# Rocketometer2148.net
KiCad netlist of a schematic drawn in EAGLE
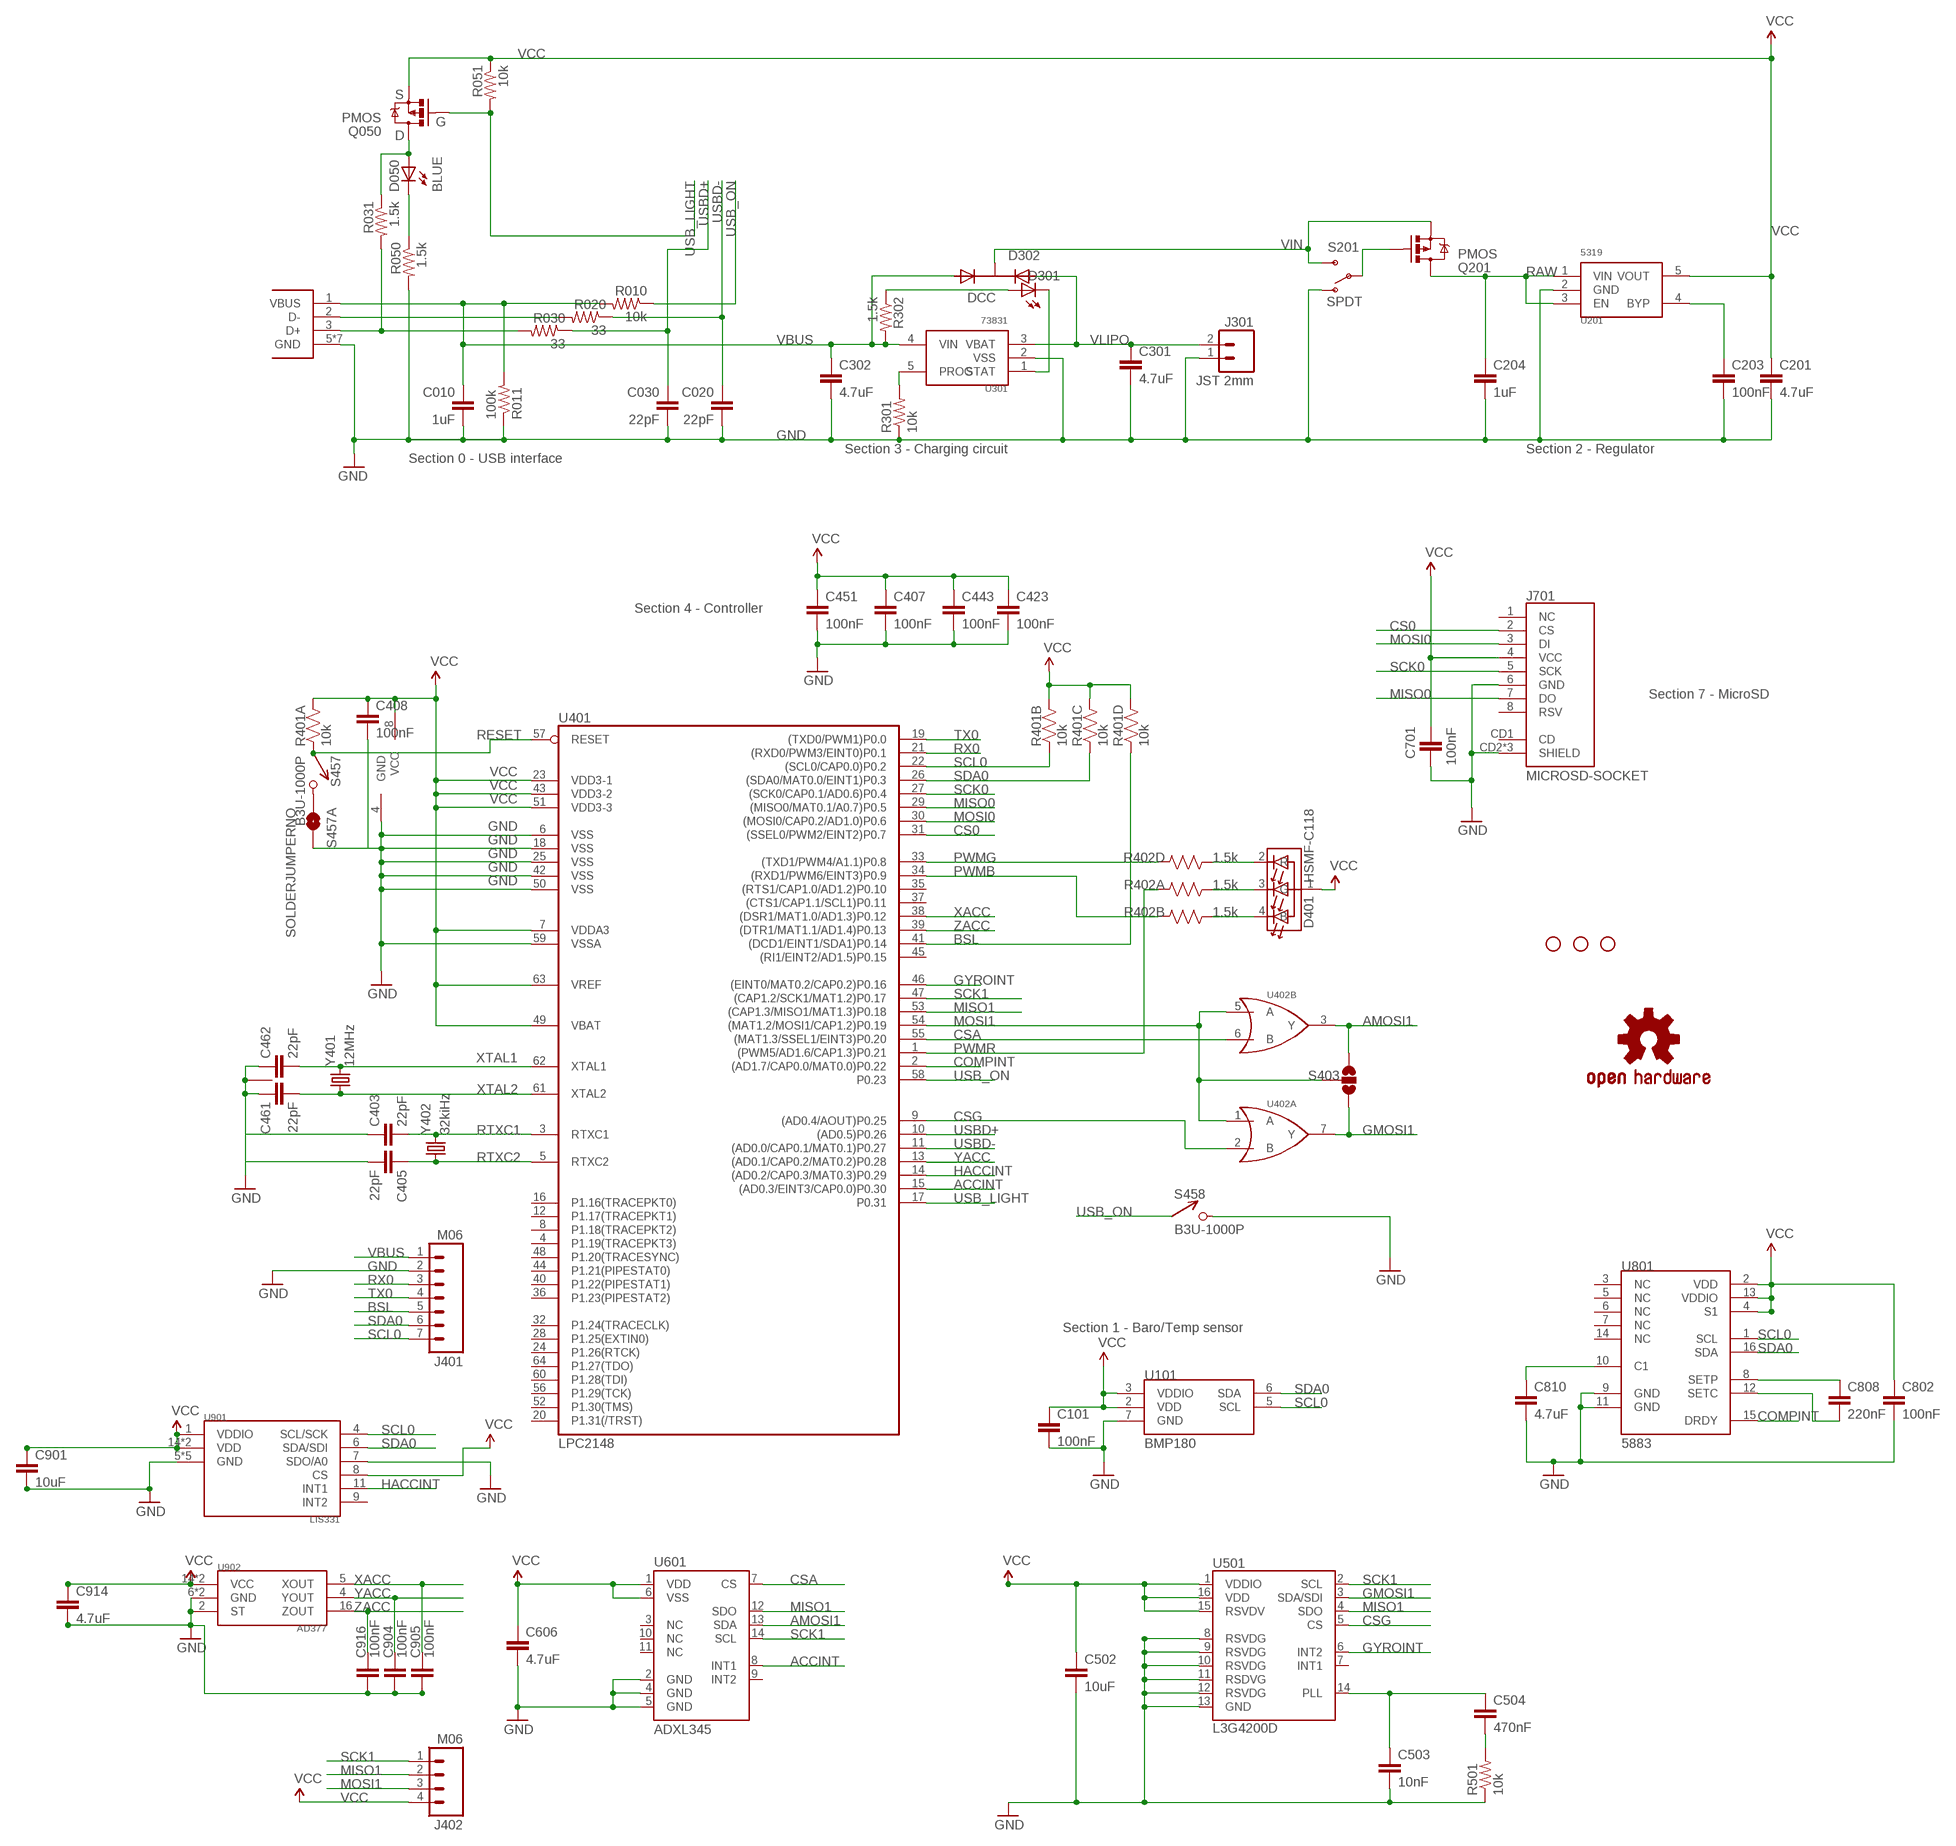
[diagram p0: schematic, sheet 1]

(export (version "E")
  (design (tool "Eeschema 10.0.6"))
  (components
    (comp (ref "C010")
      (value "1uF")
      (footprint "eagle-import:0402-CAP")
      (libsource (lib "eagle-import") (part "CAP0402-CAP"))
    )
    (comp (ref "C020")
      (value "22pF")
      (footprint "eagle-import:0402-CAP")
      (libsource (lib "eagle-import") (part "CAP0402-CAP"))
    )
    (comp (ref "C030")
      (value "22pF")
      (footprint "eagle-import:0402-CAP")
      (libsource (lib "eagle-import") (part "CAP0402-CAP"))
    )
    (comp (ref "C101")
      (value "100nF")
      (footprint "eagle-import:0402-CAP")
      (libsource (lib "eagle-import") (part "CAP0402-CAP"))
    )
    (comp (ref "C201")
      (value "4.7uF")
      (footprint "eagle-import:0402-CAP")
      (libsource (lib "eagle-import") (part "CAP0402-CAP"))
    )
    (comp (ref "C203")
      (value "100nF")
      (footprint "eagle-import:0402-CAP")
      (libsource (lib "eagle-import") (part "CAP0402-CAP"))
    )
    (comp (ref "C204")
      (value "1uF")
      (footprint "eagle-import:0402-CAP")
      (libsource (lib "eagle-import") (part "CAP0402-CAP"))
    )
    (comp (ref "C301")
      (value "4.7uF")
      (footprint "eagle-import:0402-CAP")
      (libsource (lib "eagle-import") (part "CAP0402-CAP"))
    )
    (comp (ref "C302")
      (value "4.7uF")
      (footprint "eagle-import:0402-CAP")
      (libsource (lib "eagle-import") (part "CAP0402-CAP"))
    )
    (comp (ref "C403")
      (value "22pF")
      (footprint "eagle-import:0402-CAP")
      (libsource (lib "eagle-import") (part "CAP0402-CAP"))
    )
    (comp (ref "C405")
      (value "22pF")
      (footprint "eagle-import:0402-CAP")
      (libsource (lib "eagle-import") (part "CAP0402-CAP"))
    )
    (comp (ref "C407")
      (value "100nF")
      (footprint "eagle-import:0402-CAP")
      (libsource (lib "eagle-import") (part "CAP0402-CAP"))
    )
    (comp (ref "C408")
      (value "100nF")
      (footprint "eagle-import:0402-CAP")
      (libsource (lib "eagle-import") (part "CAP0402-CAP"))
    )
    (comp (ref "C423")
      (value "100nF")
      (footprint "eagle-import:0402-CAP")
      (libsource (lib "eagle-import") (part "CAP0402-CAP"))
    )
    (comp (ref "C443")
      (value "100nF")
      (footprint "eagle-import:0402-CAP")
      (libsource (lib "eagle-import") (part "CAP0402-CAP"))
    )
    (comp (ref "C451")
      (value "100nF")
      (footprint "eagle-import:0402-CAP")
      (libsource (lib "eagle-import") (part "CAP0402-CAP"))
    )
    (comp (ref "C461")
      (value "22pF")
      (footprint "eagle-import:0402-CAP")
      (libsource (lib "eagle-import") (part "CAP0402-CAP"))
    )
    (comp (ref "C462")
      (value "22pF")
      (footprint "eagle-import:0402-CAP")
      (libsource (lib "eagle-import") (part "CAP0402-CAP"))
    )
    (comp (ref "C502")
      (value "10uF")
      (footprint "eagle-import:0603-CAP")
      (libsource (lib "eagle-import") (part "CAP0603-CAP"))
    )
    (comp (ref "C503")
      (value "10nF")
      (footprint "eagle-import:0402-CAP")
      (libsource (lib "eagle-import") (part "CAP0402-CAP"))
    )
    (comp (ref "C504")
      (value "470nF")
      (footprint "eagle-import:0402-CAP")
      (libsource (lib "eagle-import") (part "CAP0402-CAP"))
    )
    (comp (ref "C606")
      (value "4.7uF")
      (footprint "eagle-import:0402-CAP")
      (libsource (lib "eagle-import") (part "CAP0402-CAP"))
    )
    (comp (ref "C701")
      (value "100nF")
      (footprint "eagle-import:0402-CAP")
      (libsource (lib "eagle-import") (part "CAP0402-CAP"))
    )
    (comp (ref "C802")
      (value "100nF")
      (footprint "eagle-import:0402-CAP")
      (libsource (lib "eagle-import") (part "CAP0402-CAP"))
    )
    (comp (ref "C808")
      (value "220nF")
      (footprint "eagle-import:0402-CAP")
      (libsource (lib "eagle-import") (part "CAP0402-CAP"))
    )
    (comp (ref "C810")
      (value "4.7uF")
      (footprint "eagle-import:0402-CAP")
      (libsource (lib "eagle-import") (part "CAP0402-CAP"))
    )
    (comp (ref "C901")
      (value "10uF")
      (footprint "eagle-import:0603-CAP")
      (libsource (lib "eagle-import") (part "CAP0603-CAP"))
    )
    (comp (ref "C904")
      (value "100nF")
      (footprint "eagle-import:0402-CAP")
      (libsource (lib "eagle-import") (part "CAP0402-CAP"))
    )
    (comp (ref "C905")
      (value "100nF")
      (footprint "eagle-import:0402-CAP")
      (libsource (lib "eagle-import") (part "CAP0402-CAP"))
    )
    (comp (ref "C914")
      (value "4.7uF")
      (footprint "eagle-import:0402-CAP")
      (libsource (lib "eagle-import") (part "CAP0402-CAP"))
    )
    (comp (ref "C916")
      (value "100nF")
      (footprint "eagle-import:0402-CAP")
      (libsource (lib "eagle-import") (part "CAP0402-CAP"))
    )
    (comp (ref "D050")
      (value "BLUE")
      (footprint "eagle-import:LED-0603")
      (libsource (lib "eagle-import") (part "LED0603"))
    )
    (comp (ref "D301")
      (value "YELLOW")
      (footprint "eagle-import:LED-0603")
      (libsource (lib "eagle-import") (part "LED0603"))
    )
    (comp (ref "D302")
      (value "DCC")
      (footprint "eagle-import:SOT-23-3")
      (libsource (lib "eagle-import") (part "PMEG2005CT"))
    )
    (comp (ref "D401")
      (value "HSMF-C118")
      (footprint "eagle-import:HSMF-C118")
      (libsource (lib "eagle-import") (part "HSMF-C118"))
    )
    (comp (ref "J001")
      (value "USB_MICROB_JST")
      (footprint "eagle-import:UB-MC5BR3-SD204-4S")
      (libsource (lib "eagle-import") (part "USB_MICROB_JST"))
    )
    (comp (ref "J301")
      (value "JST 2mm")
      (footprint "eagle-import:JST-2-SMD")
      (libsource (lib "eagle-import") (part "M02-JST-2MM-SMT"))
    )
    (comp (ref "J401")
      (value "M06")
      (footprint "eagle-import:1X07")
      (libsource (lib "eagle-import") (part "M07"))
    )
    (comp (ref "J402")
      (value "M06")
      (footprint "eagle-import:1X04")
      (libsource (lib "eagle-import") (part "M04PTH"))
    )
    (comp (ref "J701")
      (value "MICROSD-SOCKET")
      (footprint "eagle-import:MICROSD-SOCKET-PP")
      (libsource (lib "eagle-import") (part "MICROSD-SOCKET"))
    )
    (comp (ref "JP1")
      (value "STAND-OFFTIGHT")
      (footprint "eagle-import:STAND-OFF-TIGHT")
      (libsource (lib "eagle-import") (part "STAND-OFFTIGHT"))
    )
    (comp (ref "JP2")
      (value "STAND-OFFTIGHT")
      (footprint "eagle-import:STAND-OFF-TIGHT")
      (libsource (lib "eagle-import") (part "STAND-OFFTIGHT"))
    )
    (comp (ref "JP3")
      (value "STAND-OFFTIGHT")
      (footprint "eagle-import:STAND-OFF-TIGHT")
      (libsource (lib "eagle-import") (part "STAND-OFFTIGHT"))
    )
    (comp (ref "Q050")
      (value "PMOS")
      (footprint "eagle-import:SOT23-3")
      (libsource (lib "eagle-import") (part "MOSFET-PCHANNELSMD"))
    )
    (comp (ref "Q201")
      (value "PMOS")
      (footprint "eagle-import:SOT23-3")
      (libsource (lib "eagle-import") (part "MOSFET-PCHANNELSMD"))
    )
    (comp (ref "R010")
      (value "10k")
      (footprint "eagle-import:0402-RES")
      (libsource (lib "eagle-import") (part "RESISTOR0402-RES"))
    )
    (comp (ref "R011")
      (value "100k")
      (footprint "eagle-import:0402-RES")
      (libsource (lib "eagle-import") (part "RESISTOR0402-RES"))
    )
    (comp (ref "R020")
      (value "33")
      (footprint "eagle-import:0402-RES")
      (libsource (lib "eagle-import") (part "RESISTOR0402-RES"))
    )
    (comp (ref "R030")
      (value "33")
      (footprint "eagle-import:0402-RES")
      (libsource (lib "eagle-import") (part "RESISTOR0402-RES"))
    )
    (comp (ref "R031")
      (value "1.5k")
      (footprint "eagle-import:0402-RES")
      (libsource (lib "eagle-import") (part "RESISTOR0402-RES"))
    )
    (comp (ref "R050")
      (value "1.5k")
      (footprint "eagle-import:0402-RES")
      (libsource (lib "eagle-import") (part "RESISTOR0402-RES"))
    )
    (comp (ref "R051")
      (value "10k")
      (footprint "eagle-import:0402-RES")
      (libsource (lib "eagle-import") (part "RESISTOR0402-RES"))
    )
    (comp (ref "R301")
      (value "10k")
      (footprint "eagle-import:0402-RES")
      (libsource (lib "eagle-import") (part "RESISTOR0402-RES"))
    )
    (comp (ref "R302")
      (value "1.5k")
      (footprint "eagle-import:0402-RES")
      (libsource (lib "eagle-import") (part "RESISTOR0402-RES"))
    )
    (comp (ref "R401")
      (value "10k")
      (footprint "eagle-import:CRA04")
      (fields (field (name "DIGIKEY") "CRA4S810KCT-ND"))
      (libsource (lib "eagle-import") (part "RP404"))
    )
    (comp (ref "R402")
      (value "1.5k")
      (footprint "eagle-import:CRA04")
      (fields (field (name "DIGIKEY") "CRA4S81.5KCT-ND"))
      (libsource (lib "eagle-import") (part "RP404"))
    )
    (comp (ref "R501")
      (value "10k")
      (footprint "eagle-import:0402-RES")
      (libsource (lib "eagle-import") (part "RESISTOR0402-RES"))
    )
    (comp (ref "S201")
      (value "SPDT")
      (footprint "eagle-import:AYZ0202")
      (libsource (lib "eagle-import") (part "SWITCH-SPSTSMD"))
    )
    (comp (ref "S403")
      (value "SOLDERJUMPER_2WAYS")
      (footprint "eagle-import:SJ_3")
      (libsource (lib "eagle-import") (part "SOLDERJUMPER_2WAYS"))
    )
    (comp (ref "S457")
      (value "B3U-1000P")
      (footprint "eagle-import:B3U-1000P")
      (libsource (lib "eagle-import") (part "B3U-1000P"))
    )
    (comp (ref "S457A")
      (value "SOLDERJUMPERNO")
      (footprint "eagle-import:SJ_2S-NO")
      (libsource (lib "eagle-import") (part "SOLDERJUMPERNO"))
    )
    (comp (ref "S458")
      (value "B3U-1000P")
      (footprint "eagle-import:B3U-1000P")
      (libsource (lib "eagle-import") (part "B3U-1000P"))
    )
    (comp (ref "U$2")
      (value "OSHW-LOGOS")
      (footprint "eagle-import:OSHW-LOGO-S")
      (libsource (lib "eagle-import") (part "OSHW-LOGOS"))
    )
    (comp (ref "U101")
      (value "BMP180")
      (footprint "eagle-import:BMP180")
      (libsource (lib "eagle-import") (part "BMP180"))
    )
    (comp (ref "U201")
      (value "5319")
      (footprint "eagle-import:SOT-23-5")
      (libsource (lib "eagle-import") (part "MIC5319D5"))
    )
    (comp (ref "U301")
      (value "73831")
      (footprint "eagle-import:SOT-23-5")
      (libsource (lib "eagle-import") (part "MCP73831"))
    )
    (comp (ref "U401")
      (value "LPC2148")
      (footprint "eagle-import:SQFP-S-10X10-64")
      (libsource (lib "eagle-import") (part "LPC213X"))
    )
    (comp (ref "U402")
      (value "7432")
      (footprint "eagle-import:DCU_8")
      (fields (field (name "DIGIKEY") "296-13268-1-ND"))
      (libsource (lib "eagle-import") (part "SN74LVC2G32"))
    )
    (comp (ref "U501")
      (value "L3G4200D")
      (footprint "eagle-import:LGA16-4X4")
      (libsource (lib "eagle-import") (part "L3G4200D"))
    )
    (comp (ref "U601")
      (value "ADXL345")
      (footprint "eagle-import:LGA14")
      (libsource (lib "eagle-import") (part "ADXL345"))
    )
    (comp (ref "U801")
      (value "5883")
      (footprint "eagle-import:16LPCC")
      (libsource (lib "eagle-import") (part "HMC5883LSMD"))
    )
    (comp (ref "U901")
      (value "LIS331")
      (footprint "eagle-import:LLGA16")
      (libsource (lib "eagle-import") (part "H3LIS331DL"))
    )
    (comp (ref "U902")
      (value "AD377")
      (footprint "eagle-import:ADXL377")
      (libsource (lib "eagle-import") (part "ADXL377"))
    )
    (comp (ref "Y401")
      (value "12MHz")
      (footprint "eagle-import:CRYSTAL_SMD_2MM_2_5MM")
      (libsource (lib "eagle-import") (part "CX2520"))
    )
    (comp (ref "Y402")
      (value "32kiHz")
      (footprint "eagle-import:ABS06")
      (libsource (lib "eagle-import") (part "ABS06"))
    )
  )
  (nets
    (net (code "1") (name "/ACCINT") (class "Default")
      (node (ref "U401") (pin "15") (pinfunction "(AD0.3/EINT3/CAP0.0)P0.30_15") (pintype "bidirectional"))
      (node (ref "U601") (pin "8") (pinfunction "INT1_8") (pintype "bidirectional"))
    )
    (net (code "2") (name "/AMOSI1") (class "Default")
      (node (ref "S403") (pin "1") (pinfunction "1_1") (pintype "passive"))
      (node (ref "U402") (pin "3") (pinfunction "Y_3") (pintype "bidirectional"))
      (node (ref "U601") (pin "13") (pinfunction "SDA_13") (pintype "bidirectional"))
    )
    (net (code "3") (name "/BSL") (class "Default")
      (node (ref "J401") (pin "5") (pinfunction "5_5") (pintype "passive"))
      (node (ref "R401") (pin "4") (pinfunction "1_4") (pintype "passive"))
      (node (ref "U401") (pin "41") (pinfunction "(DCD1/EINT1/SDA1)P0.14_41") (pintype "bidirectional"))
    )
    (net (code "4") (name "/COMPINT") (class "Default")
      (node (ref "U401") (pin "2") (pinfunction "(AD1.7/CAP0.0/MAT0.0)P0.22_2") (pintype "bidirectional"))
      (node (ref "U801") (pin "15") (pinfunction "DRDY_15") (pintype "bidirectional"))
    )
    (net (code "5") (name "/CS0") (class "Default")
      (node (ref "J701") (pin "2") (pinfunction "CS_2") (pintype "bidirectional"))
      (node (ref "U401") (pin "31") (pinfunction "(SSEL0/PWM2/EINT2)P0.7_31") (pintype "bidirectional"))
    )
    (net (code "6") (name "/CSA") (class "Default")
      (node (ref "U401") (pin "55") (pinfunction "(MAT1.3/SSEL1/EINT3)P0.20_55") (pintype "bidirectional"))
      (node (ref "U402") (pin "6") (pinfunction "B_6") (pintype "bidirectional"))
      (node (ref "U601") (pin "7") (pinfunction "CS_7") (pintype "bidirectional"))
    )
    (net (code "7") (name "/CSG") (class "Default")
      (node (ref "U401") (pin "9") (pinfunction "(AD0.4/AOUT)P0.25_9") (pintype "bidirectional"))
      (node (ref "U402") (pin "2") (pinfunction "B_2") (pintype "bidirectional"))
      (node (ref "U501") (pin "5") (pinfunction "CS_5") (pintype "bidirectional"))
    )
    (net (code "8") (name "/GMOSI1") (class "Default")
      (node (ref "S403") (pin "3") (pinfunction "3_3") (pintype "passive"))
      (node (ref "U402") (pin "7") (pinfunction "Y_7") (pintype "bidirectional"))
      (node (ref "U501") (pin "3") (pinfunction "SDA/SDI_3") (pintype "bidirectional"))
    )
    (net (code "9") (name "/GYROINT") (class "Default")
      (node (ref "U401") (pin "46") (pinfunction "(EINT0/MAT0.2/CAP0.2)P0.16_46") (pintype "bidirectional"))
      (node (ref "U501") (pin "6") (pinfunction "INT2_6") (pintype "bidirectional"))
    )
    (net (code "10") (name "/HACCINT") (class "Default")
      (node (ref "U401") (pin "14") (pinfunction "(AD0.2/CAP0.3/MAT0.3)P0.29_14") (pintype "bidirectional"))
      (node (ref "U901") (pin "11") (pinfunction "INT1_11") (pintype "bidirectional"))
    )
    (net (code "11") (name "/MISO0") (class "Default")
      (node (ref "J701") (pin "7") (pinfunction "DO_7") (pintype "bidirectional"))
      (node (ref "U401") (pin "29") (pinfunction "(MISO0/MAT0.1/A0.7)P0.5_29") (pintype "bidirectional"))
    )
    (net (code "12") (name "/MISO1") (class "Default")
      (node (ref "J402") (pin "2") (pinfunction "2_2") (pintype "passive"))
      (node (ref "U401") (pin "53") (pinfunction "(CAP1.3/MISO1/MAT1.3)P0.18_53") (pintype "bidirectional"))
      (node (ref "U501") (pin "4") (pinfunction "SDO_4") (pintype "bidirectional"))
      (node (ref "U601") (pin "12") (pinfunction "SDO_12") (pintype "bidirectional"))
    )
    (net (code "13") (name "/MOSI0") (class "Default")
      (node (ref "J701") (pin "3") (pinfunction "DI_3") (pintype "bidirectional"))
      (node (ref "U401") (pin "30") (pinfunction "(MOSI0/CAP0.2/AD1.0)P0.6_30") (pintype "bidirectional"))
    )
    (net (code "14") (name "/MOSI1") (class "Default")
      (node (ref "J402") (pin "3") (pinfunction "3_3") (pintype "passive"))
      (node (ref "S403") (pin "2") (pinfunction "2_2") (pintype "passive"))
      (node (ref "U401") (pin "54") (pinfunction "(MAT1.2/MOSI1/CAP1.2)P0.19_54") (pintype "bidirectional"))
      (node (ref "U402") (pin "1") (pinfunction "A_1") (pintype "bidirectional"))
      (node (ref "U402") (pin "5") (pinfunction "A_5") (pintype "bidirectional"))
    )
    (net (code "15") (name "/PWMB") (class "Default")
      (node (ref "R402") (pin "7") (pinfunction "2_7") (pintype "passive"))
      (node (ref "U401") (pin "34") (pinfunction "(RXD1/PWM6/EINT3)P0.9_34") (pintype "bidirectional"))
    )
    (net (code "16") (name "/PWMG") (class "Default")
      (node (ref "R402") (pin "5") (pinfunction "2_5") (pintype "passive"))
      (node (ref "U401") (pin "33") (pinfunction "(TXD1/PWM4/A1.1)P0.8_33") (pintype "bidirectional"))
    )
    (net (code "17") (name "/PWMR") (class "Default")
      (node (ref "R402") (pin "8") (pinfunction "2_8") (pintype "passive"))
      (node (ref "U401") (pin "1") (pinfunction "(PWM5/AD1.6/CAP1.3)P0.21_1") (pintype "bidirectional"))
    )
    (net (code "18") (name "/RAW") (class "Default")
      (node (ref "C204") (pin "1") (pinfunction "1_1") (pintype "passive"))
      (node (ref "Q201") (pin "3") (pinfunction "D_3") (pintype "passive"))
      (node (ref "U201") (pin "1") (pinfunction "VIN_1") (pintype "bidirectional"))
      (node (ref "U201") (pin "3") (pinfunction "EN_3") (pintype "bidirectional"))
    )
    (net (code "19") (name "/RESET") (class "Default")
      (node (ref "R401") (pin "1") (pinfunction "1_1") (pintype "passive"))
      (node (ref "S457") (pin "P$1") (pinfunction "1_P$1") (pintype "bidirectional"))
      (node (ref "U401") (pin "57") (pinfunction "RESET_57") (pintype "input"))
    )
    (net (code "20") (name "/RTXC1") (class "Default")
      (node (ref "C403") (pin "2") (pinfunction "2_2") (pintype "passive"))
      (node (ref "U401") (pin "3") (pinfunction "RTXC1_3") (pintype "input"))
      (node (ref "Y402") (pin "2") (pinfunction "2_2") (pintype "passive"))
    )
    (net (code "21") (name "/RTXC2") (class "Default")
      (node (ref "C405") (pin "1") (pinfunction "1_1") (pintype "passive"))
      (node (ref "U401") (pin "5") (pinfunction "RTXC2_5") (pintype "output"))
      (node (ref "Y402") (pin "1") (pinfunction "1_1") (pintype "passive"))
    )
    (net (code "22") (name "/RX0") (class "Default")
      (node (ref "J401") (pin "3") (pinfunction "3_3") (pintype "passive"))
      (node (ref "U401") (pin "21") (pinfunction "(RXD0/PWM3/EINT0)P0.1_21") (pintype "bidirectional"))
    )
    (net (code "23") (name "/SCK0") (class "Default")
      (node (ref "J701") (pin "5") (pinfunction "SCK_5") (pintype "bidirectional"))
      (node (ref "U401") (pin "27") (pinfunction "(SCK0/CAP0.1/AD0.6)P0.4_27") (pintype "bidirectional"))
    )
    (net (code "24") (name "/SCK1") (class "Default")
      (node (ref "J402") (pin "1") (pinfunction "1_1") (pintype "passive"))
      (node (ref "U401") (pin "47") (pinfunction "(CAP1.2/SCK1/MAT1.2)P0.17_47") (pintype "bidirectional"))
      (node (ref "U501") (pin "2") (pinfunction "SCL_2") (pintype "bidirectional"))
      (node (ref "U601") (pin "14") (pinfunction "SCL_14") (pintype "bidirectional"))
    )
    (net (code "25") (name "/SCL0") (class "Default")
      (node (ref "J401") (pin "7") (pinfunction "7_7") (pintype "passive"))
      (node (ref "R401") (pin "2") (pinfunction "1_2") (pintype "passive"))
      (node (ref "U101") (pin "5") (pinfunction "SCL_5") (pintype "input"))
      (node (ref "U401") (pin "22") (pinfunction "(SCL0/CAP0.0)P0.2_22") (pintype "bidirectional"))
      (node (ref "U801") (pin "1") (pinfunction "SCL_1") (pintype "bidirectional"))
      (node (ref "U901") (pin "4") (pinfunction "SCL/SCK_4") (pintype "bidirectional"))
    )
    (net (code "26") (name "/SDA0") (class "Default")
      (node (ref "J401") (pin "6") (pinfunction "6_6") (pintype "passive"))
      (node (ref "R401") (pin "3") (pinfunction "1_3") (pintype "passive"))
      (node (ref "U101") (pin "6") (pinfunction "SDA_6") (pintype "bidirectional"))
      (node (ref "U401") (pin "26") (pinfunction "(SDA0/MAT0.0/EINT1)P0.3_26") (pintype "bidirectional"))
      (node (ref "U801") (pin "16") (pinfunction "SDA_16") (pintype "bidirectional"))
      (node (ref "U901") (pin "6") (pinfunction "SDA/SDI_6") (pintype "bidirectional"))
    )
    (net (code "27") (name "/TX0") (class "Default")
      (node (ref "J401") (pin "4") (pinfunction "4_4") (pintype "passive"))
      (node (ref "U401") (pin "19") (pinfunction "(TXD0/PWM1)P0.0_19") (pintype "bidirectional"))
    )
    (net (code "28") (name "/USBD+") (class "Default")
      (node (ref "C030") (pin "1") (pinfunction "1_1") (pintype "passive"))
      (node (ref "R030") (pin "1") (pinfunction "1_1") (pintype "passive"))
      (node (ref "U401") (pin "10") (pinfunction "(AD0.5)P0.26_10") (pintype "bidirectional"))
    )
    (net (code "29") (name "/USBD-") (class "Default")
      (node (ref "C020") (pin "1") (pinfunction "1_1") (pintype "passive"))
      (node (ref "R020") (pin "1") (pinfunction "1_1") (pintype "passive"))
      (node (ref "U401") (pin "11") (pinfunction "(AD0.0/CAP0.1/MAT0.1)P0.27_11") (pintype "bidirectional"))
    )
    (net (code "30") (name "/USB_LIGHT") (class "Default")
      (node (ref "Q050") (pin "1") (pinfunction "G_1") (pintype "passive"))
      (node (ref "R051") (pin "2") (pinfunction "2_2") (pintype "passive"))
      (node (ref "U401") (pin "17") (pinfunction "P0.31_17") (pintype "output"))
    )
    (net (code "31") (name "/USB_ON") (class "Default")
      (node (ref "R010") (pin "1") (pinfunction "1_1") (pintype "passive"))
      (node (ref "S458") (pin "P$1") (pinfunction "1_P$1") (pintype "bidirectional"))
      (node (ref "U401") (pin "58") (pinfunction "P0.23_58") (pintype "bidirectional"))
    )
    (net (code "32") (name "/VBUS") (class "Default")
      (node (ref "C010") (pin "1") (pinfunction "1_1") (pintype "passive"))
      (node (ref "C302") (pin "1") (pinfunction "1_1") (pintype "passive"))
      (node (ref "D302") (pin "1") (pinfunction "A1_1") (pintype "passive"))
      (node (ref "J001") (pin "1") (pinfunction "VBUS_1") (pintype "bidirectional"))
      (node (ref "J401") (pin "1") (pinfunction "1_1") (pintype "passive"))
      (node (ref "R010") (pin "2") (pinfunction "2_2") (pintype "passive"))
      (node (ref "R011") (pin "2") (pinfunction "2_2") (pintype "passive"))
      (node (ref "R302") (pin "2") (pinfunction "2_2") (pintype "passive"))
      (node (ref "U301") (pin "4") (pinfunction "VIN_4") (pintype "bidirectional"))
    )
    (net (code "33") (name "/VIN") (class "Default")
      (node (ref "D302") (pin "3") (pinfunction "K_3") (pintype "passive"))
      (node (ref "Q201") (pin "2") (pinfunction "S_2") (pintype "passive"))
      (node (ref "S201") (pin "3") (pinfunction "S_3") (pintype "passive"))
    )
    (net (code "34") (name "/VLIPO") (class "Default")
      (node (ref "C301") (pin "1") (pinfunction "1_1") (pintype "passive"))
      (node (ref "D302") (pin "2") (pinfunction "A2_2") (pintype "passive"))
      (node (ref "J301") (pin "2") (pinfunction "2_2") (pintype "passive"))
      (node (ref "U301") (pin "3") (pinfunction "VBAT_3") (pintype "bidirectional"))
    )
    (net (code "35") (name "/XACC") (class "Default")
      (node (ref "C905") (pin "1") (pinfunction "1_1") (pintype "passive"))
      (node (ref "U401") (pin "38") (pinfunction "(DSR1/MAT1.0/AD1.3)P0.12_38") (pintype "bidirectional"))
      (node (ref "U902") (pin "5") (pinfunction "XOUT_5") (pintype "bidirectional"))
    )
    (net (code "36") (name "/XTAL1") (class "Default")
      (node (ref "C462") (pin "2") (pinfunction "2_2") (pintype "passive"))
      (node (ref "U401") (pin "62") (pinfunction "XTAL1_62") (pintype "input"))
      (node (ref "Y401") (pin "3") (pinfunction "2_3") (pintype "passive"))
    )
    (net (code "37") (name "/XTAL2") (class "Default")
      (node (ref "C461") (pin "2") (pinfunction "2_2") (pintype "passive"))
      (node (ref "U401") (pin "61") (pinfunction "XTAL2_61") (pintype "output"))
      (node (ref "Y401") (pin "1") (pinfunction "1_1") (pintype "passive"))
    )
    (net (code "38") (name "/YACC") (class "Default")
      (node (ref "C904") (pin "1") (pinfunction "1_1") (pintype "passive"))
      (node (ref "U401") (pin "13") (pinfunction "(AD0.1/CAP0.2/MAT0.2)P0.28_13") (pintype "bidirectional"))
      (node (ref "U902") (pin "4") (pinfunction "YOUT_4") (pintype "bidirectional"))
    )
    (net (code "39") (name "/ZACC") (class "Default")
      (node (ref "C916") (pin "1") (pinfunction "1_1") (pintype "passive"))
      (node (ref "U401") (pin "39") (pinfunction "(DTR1/MAT1.1/AD1.4)P0.13_39") (pintype "bidirectional"))
      (node (ref "U902") (pin "16") (pinfunction "ZOUT_16") (pintype "bidirectional"))
    )
    (net (code "40") (name "GND") (class "Default")
      (node (ref "C010") (pin "2") (pinfunction "2_2") (pintype "passive"))
      (node (ref "C020") (pin "2") (pinfunction "2_2") (pintype "passive"))
      (node (ref "C030") (pin "2") (pinfunction "2_2") (pintype "passive"))
      (node (ref "C101") (pin "2") (pinfunction "2_2") (pintype "passive"))
      (node (ref "C201") (pin "2") (pinfunction "2_2") (pintype "passive"))
      (node (ref "C203") (pin "2") (pinfunction "2_2") (pintype "passive"))
      (node (ref "C204") (pin "2") (pinfunction "2_2") (pintype "passive"))
      (node (ref "C301") (pin "2") (pinfunction "2_2") (pintype "passive"))
      (node (ref "C302") (pin "2") (pinfunction "2_2") (pintype "passive"))
      (node (ref "C403") (pin "1") (pinfunction "1_1") (pintype "passive"))
      (node (ref "C405") (pin "2") (pinfunction "2_2") (pintype "passive"))
      (node (ref "C407") (pin "2") (pinfunction "2_2") (pintype "passive"))
      (node (ref "C408") (pin "2") (pinfunction "2_2") (pintype "passive"))
      (node (ref "C423") (pin "2") (pinfunction "2_2") (pintype "passive"))
      (node (ref "C443") (pin "2") (pinfunction "2_2") (pintype "passive"))
      (node (ref "C451") (pin "2") (pinfunction "2_2") (pintype "passive"))
      (node (ref "C461") (pin "1") (pinfunction "1_1") (pintype "passive"))
      (node (ref "C462") (pin "1") (pinfunction "1_1") (pintype "passive"))
      (node (ref "C502") (pin "2") (pinfunction "2_2") (pintype "passive"))
      (node (ref "C503") (pin "2") (pinfunction "2_2") (pintype "passive"))
      (node (ref "C606") (pin "2") (pinfunction "2_2") (pintype "passive"))
      (node (ref "C701") (pin "2") (pinfunction "2_2") (pintype "passive"))
      (node (ref "C802") (pin "2") (pinfunction "2_2") (pintype "passive"))
      (node (ref "C810") (pin "2") (pinfunction "2_2") (pintype "passive"))
      (node (ref "C901") (pin "2") (pinfunction "2_2") (pintype "passive"))
      (node (ref "C904") (pin "2") (pinfunction "2_2") (pintype "passive"))
      (node (ref "C905") (pin "2") (pinfunction "2_2") (pintype "passive"))
      (node (ref "C914") (pin "2") (pinfunction "2_2") (pintype "passive"))
      (node (ref "C916") (pin "2") (pinfunction "2_2") (pintype "passive"))
      (node (ref "J001") (pin "5") (pinfunction "GND_5") (pintype "bidirectional"))
      (node (ref "J001") (pin "P$10") (pinfunction "GND_P$10") (pintype "bidirectional"))
      (node (ref "J001") (pin "P$11") (pinfunction "GND_P$11") (pintype "bidirectional"))
      (node (ref "J001") (pin "P$6") (pinfunction "GND_P$6") (pintype "bidirectional"))
      (node (ref "J001") (pin "P$7") (pinfunction "GND_P$7") (pintype "bidirectional"))
      (node (ref "J001") (pin "P$8") (pinfunction "GND_P$8") (pintype "bidirectional"))
      (node (ref "J001") (pin "P$9") (pinfunction "GND_P$9") (pintype "bidirectional"))
      (node (ref "J301") (pin "1") (pinfunction "1_1") (pintype "passive"))
      (node (ref "J401") (pin "2") (pinfunction "2_2") (pintype "passive"))
      (node (ref "J701") (pin "6") (pinfunction "GND_6") (pintype "bidirectional"))
      (node (ref "J701") (pin "CD2") (pinfunction "SHIELD_CD2") (pintype "bidirectional"))
      (node (ref "J701") (pin "GND1") (pinfunction "SHIELD_GND1") (pintype "bidirectional"))
      (node (ref "J701") (pin "GND3") (pinfunction "SHIELD_GND3") (pintype "bidirectional"))
      (node (ref "R011") (pin "1") (pinfunction "1_1") (pintype "passive"))
      (node (ref "R050") (pin "2") (pinfunction "2_2") (pintype "passive"))
      (node (ref "R301") (pin "1") (pinfunction "1_1") (pintype "passive"))
      (node (ref "R501") (pin "1") (pinfunction "1_1") (pintype "passive"))
      (node (ref "S201") (pin "1") (pinfunction "O_1") (pintype "passive"))
      (node (ref "S457A") (pin "2") (pinfunction "2_2") (pintype "passive"))
      (node (ref "S458") (pin "P$2") (pinfunction "2_P$2") (pintype "bidirectional"))
      (node (ref "U101") (pin "7") (pinfunction "GND_7") (pintype "power_in"))
      (node (ref "U201") (pin "2") (pinfunction "GND_2") (pintype "bidirectional"))
      (node (ref "U301") (pin "2") (pinfunction "VSS_2") (pintype "bidirectional"))
      (node (ref "U401") (pin "18") (pinfunction "VSS_18") (pintype "power_in"))
      (node (ref "U401") (pin "25") (pinfunction "VSS_25") (pintype "power_in"))
      (node (ref "U401") (pin "42") (pinfunction "VSS_42") (pintype "power_in"))
      (node (ref "U401") (pin "50") (pinfunction "VSS_50") (pintype "power_in"))
      (node (ref "U401") (pin "59") (pinfunction "VSSA_59") (pintype "power_in"))
      (node (ref "U401") (pin "6") (pinfunction "VSS_6") (pintype "power_in"))
      (node (ref "U402") (pin "4") (pinfunction "GND_4") (pintype "bidirectional"))
      (node (ref "U501") (pin "10") (pinfunction "RSVDG_10") (pintype "bidirectional"))
      (node (ref "U501") (pin "11") (pinfunction "RSDVG_11") (pintype "bidirectional"))
      (node (ref "U501") (pin "12") (pinfunction "RSVDG_12") (pintype "bidirectional"))
      (node (ref "U501") (pin "13") (pinfunction "GND_13") (pintype "bidirectional"))
      (node (ref "U501") (pin "8") (pinfunction "RSVDG_8") (pintype "bidirectional"))
      (node (ref "U501") (pin "9") (pinfunction "RSVDG_9") (pintype "bidirectional"))
      (node (ref "U601") (pin "2") (pinfunction "GND_2") (pintype "bidirectional"))
      (node (ref "U601") (pin "4") (pinfunction "GND_4") (pintype "bidirectional"))
      (node (ref "U601") (pin "5") (pinfunction "GND_5") (pintype "bidirectional"))
      (node (ref "U801") (pin "11") (pinfunction "GND_11") (pintype "bidirectional"))
      (node (ref "U801") (pin "9") (pinfunction "GND_9") (pintype "bidirectional"))
      (node (ref "U901") (pin "10") (pinfunction "GND_10") (pintype "bidirectional"))
      (node (ref "U901") (pin "12") (pinfunction "GND_12") (pintype "bidirectional"))
      (node (ref "U901") (pin "13") (pinfunction "GND_13") (pintype "bidirectional"))
      (node (ref "U901") (pin "16") (pinfunction "GND_16") (pintype "bidirectional"))
      (node (ref "U901") (pin "5") (pinfunction "GND_5") (pintype "bidirectional"))
      (node (ref "U901") (pin "7") (pinfunction "SDO/A0_7") (pintype "bidirectional"))
      (node (ref "U902") (pin "2") (pinfunction "ST_2") (pintype "bidirectional"))
      (node (ref "U902") (pin "6") (pinfunction "GND_6") (pintype "bidirectional"))
      (node (ref "U902") (pin "7") (pinfunction "GND_7") (pintype "bidirectional"))
      (node (ref "Y401") (pin "2") (pinfunction "1_2") (pintype "bidirectional"))
      (node (ref "Y401") (pin "4") (pinfunction "1_4") (pintype "bidirectional"))
    )
    (net (code "41") (name "Net-(C504-Pad2)") (class "Default")
      (node (ref "C504") (pin "2") (pinfunction "2_2") (pintype "passive"))
      (node (ref "R501") (pin "2") (pinfunction "2_2") (pintype "passive"))
    )
    (net (code "42") (name "Net-(D050-PadC)") (class "Default")
      (node (ref "D050") (pin "C") (pinfunction "C_C") (pintype "passive"))
      (node (ref "R050") (pin "1") (pinfunction "1_1") (pintype "passive"))
    )
    (net (code "43") (name "Net-(D301-PadA)") (class "Default")
      (node (ref "D301") (pin "A") (pinfunction "A_A") (pintype "passive"))
      (node (ref "R302") (pin "1") (pinfunction "1_1") (pintype "passive"))
    )
    (net (code "44") (name "Net-(D401-B)") (class "Default")
      (node (ref "D401") (pin "4") (pinfunction "B_4") (pintype "passive"))
      (node (ref "R402") (pin "2") (pinfunction "1_2") (pintype "passive"))
    )
    (net (code "45") (name "Net-(D401-G)") (class "Default")
      (node (ref "D401") (pin "3") (pinfunction "G_3") (pintype "passive"))
      (node (ref "R402") (pin "1") (pinfunction "1_1") (pintype "passive"))
    )
    (net (code "46") (name "Net-(D401-R)") (class "Default")
      (node (ref "D401") (pin "2") (pinfunction "R_2") (pintype "passive"))
      (node (ref "R402") (pin "4") (pinfunction "1_4") (pintype "passive"))
    )
    (net (code "47") (name "Net-(J001-D+)") (class "Default")
      (node (ref "J001") (pin "3") (pinfunction "D+_3") (pintype "bidirectional"))
      (node (ref "R030") (pin "2") (pinfunction "2_2") (pintype "passive"))
      (node (ref "R031") (pin "2") (pinfunction "2_2") (pintype "passive"))
    )
    (net (code "48") (name "Net-(J001-D-)") (class "Default")
      (node (ref "J001") (pin "2") (pinfunction "D-_2") (pintype "bidirectional"))
      (node (ref "R020") (pin "2") (pinfunction "2_2") (pintype "passive"))
    )
    (net (code "49") (name "Net-(Q050-D)") (class "Default")
      (node (ref "D050") (pin "A") (pinfunction "A_A") (pintype "passive"))
      (node (ref "Q050") (pin "3") (pinfunction "D_3") (pintype "passive"))
      (node (ref "R031") (pin "1") (pinfunction "1_1") (pintype "passive"))
    )
    (net (code "50") (name "Net-(Q201-G)") (class "Default")
      (node (ref "Q201") (pin "1") (pinfunction "G_1") (pintype "passive"))
      (node (ref "S201") (pin "2") (pinfunction "P_2") (pintype "passive"))
    )
    (net (code "51") (name "Net-(S457-2)") (class "Default")
      (node (ref "S457") (pin "P$2") (pinfunction "2_P$2") (pintype "bidirectional"))
      (node (ref "S457A") (pin "1") (pinfunction "1_1") (pintype "passive"))
    )
    (net (code "52") (name "Net-(U201-BYP)") (class "Default")
      (node (ref "C203") (pin "1") (pinfunction "1_1") (pintype "passive"))
      (node (ref "U201") (pin "4") (pinfunction "BYP_4") (pintype "bidirectional"))
    )
    (net (code "53") (name "Net-(U301-PROG)") (class "Default")
      (node (ref "R301") (pin "2") (pinfunction "2_2") (pintype "passive"))
      (node (ref "U301") (pin "5") (pinfunction "PROG_5") (pintype "bidirectional"))
    )
    (net (code "54") (name "Net-(U301-STAT)") (class "Default")
      (node (ref "D301") (pin "C") (pinfunction "C_C") (pintype "passive"))
      (node (ref "U301") (pin "1") (pinfunction "STAT_1") (pintype "bidirectional"))
    )
    (net (code "55") (name "Net-(U501-PLL)") (class "Default")
      (node (ref "C503") (pin "1") (pinfunction "1_1") (pintype "passive"))
      (node (ref "C504") (pin "1") (pinfunction "1_1") (pintype "passive"))
      (node (ref "U501") (pin "14") (pinfunction "PLL_14") (pintype "bidirectional"))
    )
    (net (code "56") (name "Net-(U801-C1)") (class "Default")
      (node (ref "C810") (pin "1") (pinfunction "1_1") (pintype "passive"))
      (node (ref "U801") (pin "10") (pinfunction "C1_10") (pintype "bidirectional"))
    )
    (net (code "57") (name "Net-(U801-SETC)") (class "Default")
      (node (ref "C808") (pin "2") (pinfunction "2_2") (pintype "passive"))
      (node (ref "U801") (pin "12") (pinfunction "SETC_12") (pintype "bidirectional"))
    )
    (net (code "58") (name "Net-(U801-SETP)") (class "Default")
      (node (ref "C808") (pin "1") (pinfunction "1_1") (pintype "passive"))
      (node (ref "U801") (pin "8") (pinfunction "SETP_8") (pintype "bidirectional"))
    )
    (net (code "59") (name "VCC") (class "Default")
      (node (ref "C101") (pin "1") (pinfunction "1_1") (pintype "passive"))
      (node (ref "C201") (pin "1") (pinfunction "1_1") (pintype "passive"))
      (node (ref "C407") (pin "1") (pinfunction "1_1") (pintype "passive"))
      (node (ref "C408") (pin "1") (pinfunction "1_1") (pintype "passive"))
      (node (ref "C423") (pin "1") (pinfunction "1_1") (pintype "passive"))
      (node (ref "C443") (pin "1") (pinfunction "1_1") (pintype "passive"))
      (node (ref "C451") (pin "1") (pinfunction "1_1") (pintype "passive"))
      (node (ref "C502") (pin "1") (pinfunction "1_1") (pintype "passive"))
      (node (ref "C606") (pin "1") (pinfunction "1_1") (pintype "passive"))
      (node (ref "C701") (pin "1") (pinfunction "1_1") (pintype "passive"))
      (node (ref "C802") (pin "1") (pinfunction "1_1") (pintype "passive"))
      (node (ref "C901") (pin "1") (pinfunction "1_1") (pintype "passive"))
      (node (ref "C914") (pin "1") (pinfunction "1_1") (pintype "passive"))
      (node (ref "D401") (pin "1") (pinfunction "A_1") (pintype "passive"))
      (node (ref "J402") (pin "4") (pinfunction "4_4") (pintype "passive"))
      (node (ref "J701") (pin "4") (pinfunction "VCC_4") (pintype "bidirectional"))
      (node (ref "Q050") (pin "2") (pinfunction "S_2") (pintype "passive"))
      (node (ref "R051") (pin "1") (pinfunction "1_1") (pintype "passive"))
      (node (ref "R401") (pin "5") (pinfunction "2_5") (pintype "passive"))
      (node (ref "R401") (pin "6") (pinfunction "2_6") (pintype "passive"))
      (node (ref "R401") (pin "7") (pinfunction "2_7") (pintype "passive"))
      (node (ref "R401") (pin "8") (pinfunction "2_8") (pintype "passive"))
      (node (ref "U101") (pin "2") (pinfunction "VDD_2") (pintype "power_in"))
      (node (ref "U101") (pin "3") (pinfunction "VDDIO_3") (pintype "power_in"))
      (node (ref "U201") (pin "5") (pinfunction "VOUT_5") (pintype "bidirectional"))
      (node (ref "U401") (pin "23") (pinfunction "VDD3-1_23") (pintype "power_in"))
      (node (ref "U401") (pin "43") (pinfunction "VDD3-2_43") (pintype "power_in"))
      (node (ref "U401") (pin "49") (pinfunction "VBAT_49") (pintype "power_in"))
      (node (ref "U401") (pin "51") (pinfunction "VDD3-3_51") (pintype "power_in"))
      (node (ref "U401") (pin "63") (pinfunction "VREF_63") (pintype "input"))
      (node (ref "U401") (pin "7") (pinfunction "VDDA3_7") (pintype "power_in"))
      (node (ref "U402") (pin "8") (pinfunction "VCC_8") (pintype "bidirectional"))
      (node (ref "U501") (pin "1") (pinfunction "VDDIO_1") (pintype "bidirectional"))
      (node (ref "U501") (pin "15") (pinfunction "RSVDV_15") (pintype "bidirectional"))
      (node (ref "U501") (pin "16") (pinfunction "VDD_16") (pintype "bidirectional"))
      (node (ref "U601") (pin "1") (pinfunction "VDD_1") (pintype "bidirectional"))
      (node (ref "U601") (pin "6") (pinfunction "VSS_6") (pintype "bidirectional"))
      (node (ref "U801") (pin "13") (pinfunction "VDDIO_13") (pintype "bidirectional"))
      (node (ref "U801") (pin "2") (pinfunction "VDD_2") (pintype "bidirectional"))
      (node (ref "U801") (pin "4") (pinfunction "S1_4") (pintype "bidirectional"))
      (node (ref "U901") (pin "1") (pinfunction "VDDIO_1") (pintype "bidirectional"))
      (node (ref "U901") (pin "14") (pinfunction "VDD_14") (pintype "bidirectional"))
      (node (ref "U901") (pin "15") (pinfunction "VDD_15") (pintype "bidirectional"))
      (node (ref "U901") (pin "8") (pinfunction "CS_8") (pintype "bidirectional"))
      (node (ref "U902") (pin "14") (pinfunction "VCC_14") (pintype "bidirectional"))
      (node (ref "U902") (pin "15") (pinfunction "VCC_15") (pintype "bidirectional"))
    )
    (net (code "60") (name "unconnected-(J701-CD-PadCD1)") (class "Default")
      (node (ref "J701") (pin "CD1") (pinfunction "CD_CD1") (pintype "bidirectional"))
    )
    (net (code "61") (name "unconnected-(J701-NC-Pad1)") (class "Default")
      (node (ref "J701") (pin "1") (pinfunction "NC_1") (pintype "bidirectional"))
    )
    (net (code "62") (name "unconnected-(J701-RSV-Pad8)") (class "Default")
      (node (ref "J701") (pin "8") (pinfunction "RSV_8") (pintype "bidirectional"))
    )
    (net (code "63") (name "unconnected-(U401-(CTS1{slash}CAP1.1{slash}SCL1)P0.11-Pad37)") (class "Default")
      (node (ref "U401") (pin "37") (pinfunction "(CTS1/CAP1.1/SCL1)P0.11_37") (pintype "bidirectional"))
    )
    (net (code "64") (name "unconnected-(U401-(RI1{slash}EINT2{slash}AD1.5)P0.15-Pad45)") (class "Default")
      (node (ref "U401") (pin "45") (pinfunction "(RI1/EINT2/AD1.5)P0.15_45") (pintype "bidirectional"))
    )
    (net (code "65") (name "unconnected-(U401-(RTS1{slash}CAP1.0{slash}AD1.2)P0.10-Pad35)") (class "Default")
      (node (ref "U401") (pin "35") (pinfunction "(RTS1/CAP1.0/AD1.2)P0.10_35") (pintype "bidirectional"))
    )
    (net (code "66") (name "unconnected-(U401-P1.16(TRACEPKT0)-Pad16)") (class "Default")
      (node (ref "U401") (pin "16") (pinfunction "P1.16(TRACEPKT0)_16") (pintype "bidirectional"))
    )
    (net (code "67") (name "unconnected-(U401-P1.17(TRACEPKT1)-Pad12)") (class "Default")
      (node (ref "U401") (pin "12") (pinfunction "P1.17(TRACEPKT1)_12") (pintype "bidirectional"))
    )
    (net (code "68") (name "unconnected-(U401-P1.18(TRACEPKT2)-Pad8)") (class "Default")
      (node (ref "U401") (pin "8") (pinfunction "P1.18(TRACEPKT2)_8") (pintype "bidirectional"))
    )
    (net (code "69") (name "unconnected-(U401-P1.19(TRACEPKT3)-Pad4)") (class "Default")
      (node (ref "U401") (pin "4") (pinfunction "P1.19(TRACEPKT3)_4") (pintype "bidirectional"))
    )
    (net (code "70") (name "unconnected-(U401-P1.20(TRACESYNC)-Pad48)") (class "Default")
      (node (ref "U401") (pin "48") (pinfunction "P1.20(TRACESYNC)_48") (pintype "bidirectional"))
    )
    (net (code "71") (name "unconnected-(U401-P1.21(PIPESTAT0)-Pad44)") (class "Default")
      (node (ref "U401") (pin "44") (pinfunction "P1.21(PIPESTAT0)_44") (pintype "bidirectional"))
    )
    (net (code "72") (name "unconnected-(U401-P1.22(PIPESTAT1)-Pad40)") (class "Default")
      (node (ref "U401") (pin "40") (pinfunction "P1.22(PIPESTAT1)_40") (pintype "bidirectional"))
    )
    (net (code "73") (name "unconnected-(U401-P1.23(PIPESTAT2)-Pad36)") (class "Default")
      (node (ref "U401") (pin "36") (pinfunction "P1.23(PIPESTAT2)_36") (pintype "bidirectional"))
    )
    (net (code "74") (name "unconnected-(U401-P1.24(TRACECLK)-Pad32)") (class "Default")
      (node (ref "U401") (pin "32") (pinfunction "P1.24(TRACECLK)_32") (pintype "bidirectional"))
    )
    (net (code "75") (name "unconnected-(U401-P1.25(EXTIN0)-Pad28)") (class "Default")
      (node (ref "U401") (pin "28") (pinfunction "P1.25(EXTIN0)_28") (pintype "bidirectional"))
    )
    (net (code "76") (name "unconnected-(U401-P1.26(RTCK)-Pad24)") (class "Default")
      (node (ref "U401") (pin "24") (pinfunction "P1.26(RTCK)_24") (pintype "bidirectional"))
    )
    (net (code "77") (name "unconnected-(U401-P1.27(TDO)-Pad64)") (class "Default")
      (node (ref "U401") (pin "64") (pinfunction "P1.27(TDO)_64") (pintype "bidirectional"))
    )
    (net (code "78") (name "unconnected-(U401-P1.28(TDI)-Pad60)") (class "Default")
      (node (ref "U401") (pin "60") (pinfunction "P1.28(TDI)_60") (pintype "bidirectional"))
    )
    (net (code "79") (name "unconnected-(U401-P1.29(TCK)-Pad56)") (class "Default")
      (node (ref "U401") (pin "56") (pinfunction "P1.29(TCK)_56") (pintype "bidirectional"))
    )
    (net (code "80") (name "unconnected-(U401-P1.30(TMS)-Pad52)") (class "Default")
      (node (ref "U401") (pin "52") (pinfunction "P1.30(TMS)_52") (pintype "bidirectional"))
    )
    (net (code "81") (name "unconnected-(U401-P1.31({slash}TRST)-Pad20)") (class "Default")
      (node (ref "U401") (pin "20") (pinfunction "P1.31(/TRST)_20") (pintype "bidirectional"))
    )
    (net (code "82") (name "unconnected-(U501-INT1-Pad7)") (class "Default")
      (node (ref "U501") (pin "7") (pinfunction "INT1_7") (pintype "bidirectional"))
    )
    (net (code "83") (name "unconnected-(U601-INT2-Pad9)") (class "Default")
      (node (ref "U601") (pin "9") (pinfunction "INT2_9") (pintype "bidirectional"))
    )
    (net (code "84") (name "unconnected-(U601-NC-Pad3)") (class "Default")
      (node (ref "U601") (pin "3") (pinfunction "NC_3") (pintype "bidirectional"))
    )
    (net (code "85") (name "unconnected-(U601-NC-Pad10)") (class "Default")
      (node (ref "U601") (pin "10") (pinfunction "NC_10") (pintype "bidirectional"))
    )
    (net (code "86") (name "unconnected-(U601-NC-Pad11)") (class "Default")
      (node (ref "U601") (pin "11") (pinfunction "NC_11") (pintype "bidirectional"))
    )
    (net (code "87") (name "unconnected-(U801-NC-Pad3)") (class "Default")
      (node (ref "U801") (pin "3") (pinfunction "NC_3") (pintype "bidirectional"))
    )
    (net (code "88") (name "unconnected-(U801-NC-Pad5)") (class "Default")
      (node (ref "U801") (pin "5") (pinfunction "NC_5") (pintype "bidirectional"))
    )
    (net (code "89") (name "unconnected-(U801-NC-Pad6)") (class "Default")
      (node (ref "U801") (pin "6") (pinfunction "NC_6") (pintype "bidirectional"))
    )
    (net (code "90") (name "unconnected-(U801-NC-Pad7)") (class "Default")
      (node (ref "U801") (pin "7") (pinfunction "NC_7") (pintype "bidirectional"))
    )
    (net (code "91") (name "unconnected-(U801-NC-Pad14)") (class "Default")
      (node (ref "U801") (pin "14") (pinfunction "NC_14") (pintype "bidirectional"))
    )
    (net (code "92") (name "unconnected-(U901-INT2-Pad9)") (class "Default")
      (node (ref "U901") (pin "9") (pinfunction "INT2_9") (pintype "bidirectional"))
    )
  )
)
